# sun_siphon.net
KiCad netlist of a schematic drawn in Altium Designer
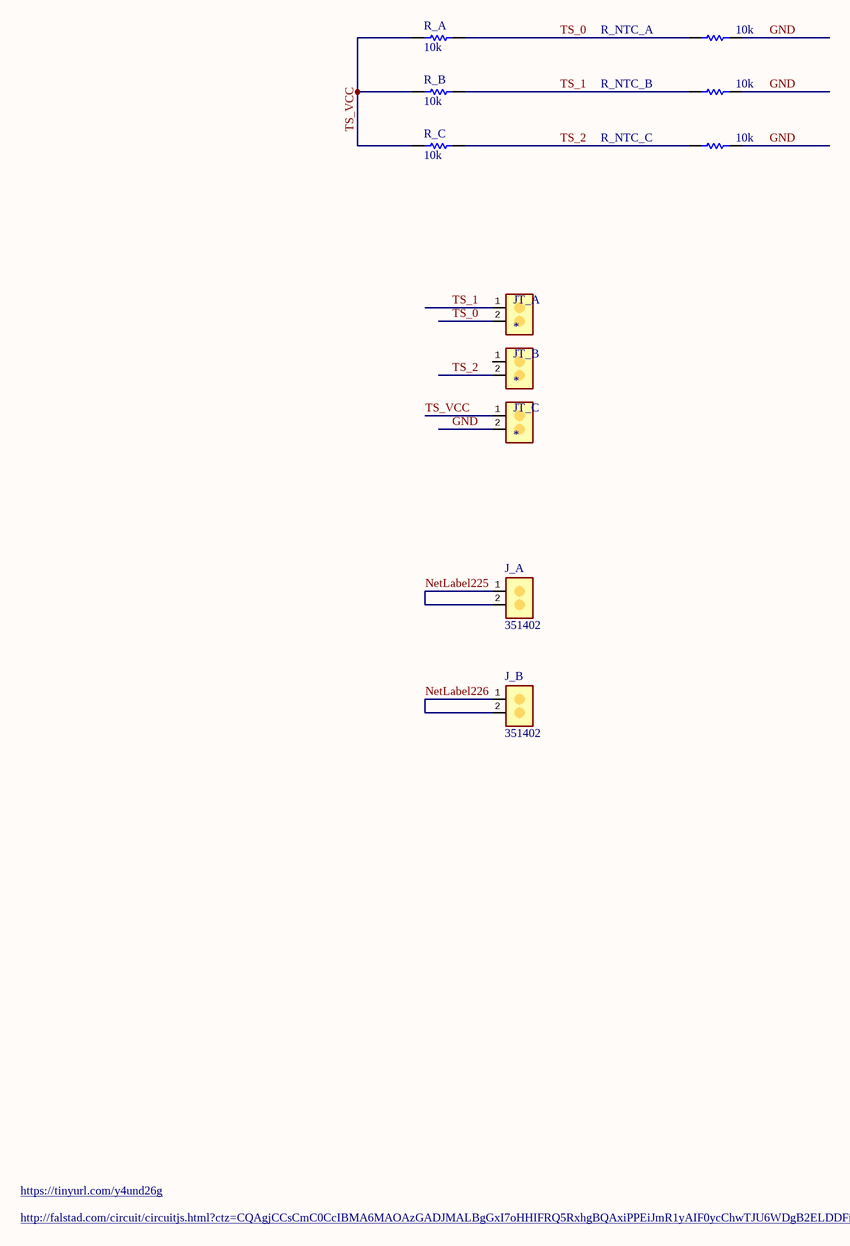
[diagram p0: sun_siphon.SchDoc]

(export (version "E")
  (design (tool "Eeschema 10.0.6"))
  (components
    (comp (ref "JT_A")
      (value "*")
      (footprint "MOLEX_1041880210")
      (description "J - JACK - POWER - MOLEX 1041880210")
      (fields (field (name "LCSC PART #") "C565283"))
      (libsource (lib "*") (part "1041880210"))
    )
    (comp (ref "JT_B")
      (value "*")
      (footprint "MOLEX_1041880210")
      (description "J - JACK - POWER - MOLEX 1041880210")
      (fields (field (name "LCSC PART #") "C565283"))
      (libsource (lib "*") (part "1041880210"))
    )
    (comp (ref "JT_C")
      (value "*")
      (footprint "MOLEX_1041880210")
      (description "J - JACK - POWER - MOLEX 1041880210")
      (fields (field (name "LCSC PART #") "C565283"))
      (libsource (lib "*") (part "1041880210"))
    )
    (comp (ref "J_A")
      (value "351402")
      (footprint "Adels-Contact_351402")
      (description "J - JACK - POWER - SMDflat 545/ 2 - RIGHT - MALE")
      (fields (field (name "LCSC PART #") "X"))
      (libsource (lib "JLC_PCB") (part "351402"))
    )
    (comp (ref "J_B")
      (value "351402")
      (footprint "Adels-Contact_351402")
      (description "J - JACK - POWER - SMDflat 545/ 2 - RIGHT - MALE")
      (fields (field (name "LCSC PART #") "X"))
      (libsource (lib "JLC_PCB") (part "351402"))
    )
    (comp (ref "R_A")
      (value "10k")
      (footprint "R_0402")
      (description "R - RESISTOR - SMD - 10k - 1% - 0402")
      (fields (field (name "LCSC PART #") "C25744") (field (name "Comment") "0402WGF1002TCE"))
      (libsource (lib "JLC_PCB") (part "0402WGF1002TCE"))
    )
    (comp (ref "R_B")
      (value "10k")
      (footprint "R_0402")
      (description "R - RESISTOR - SMD - 10k - 1% - 0402")
      (fields (field (name "LCSC PART #") "C25744") (field (name "Comment") "0402WGF1002TCE"))
      (libsource (lib "JLC_PCB") (part "0402WGF1002TCE"))
    )
    (comp (ref "R_C")
      (value "10k")
      (footprint "R_0402")
      (description "R - RESISTOR - SMD - 10k - 1% - 0402")
      (fields (field (name "LCSC PART #") "C25744") (field (name "Comment") "0402WGF1002TCE"))
      (libsource (lib "JLC_PCB") (part "0402WGF1002TCE"))
    )
    (comp (ref "R_NTC_A")
      (value "10k")
      (footprint "R_0402")
      (description "RT - NTC THERMISTOR - 10k - 1% - 0402")
      (fields (field (name "LCSC PART #") "C77131") (field (name "Comment") "NCP15XH103F03RC"))
      (libsource (lib "JLC_PCB") (part "NCP15XH103F03RC"))
    )
    (comp (ref "R_NTC_B")
      (value "10k")
      (footprint "R_0402")
      (description "RT - NTC THERMISTOR - 10k - 1% - 0402")
      (fields (field (name "LCSC PART #") "C77131") (field (name "Comment") "NCP15XH103F03RC"))
      (libsource (lib "JLC_PCB") (part "NCP15XH103F03RC"))
    )
    (comp (ref "R_NTC_C")
      (value "10k")
      (footprint "R_0402")
      (description "RT - NTC THERMISTOR - 10k - 1% - 0402")
      (fields (field (name "LCSC PART #") "C77131") (field (name "Comment") "NCP15XH103F03RC"))
      (libsource (lib "JLC_PCB") (part "NCP15XH103F03RC"))
    )
  )
  (nets
    (net (code "1") (name "/GND") (class "Default")
      (node (ref "JT_C") (pin "2") (pinfunction "2_2") (pintype "passive"))
      (node (ref "R_NTC_A") (pin "1") (pinfunction "1_1") (pintype "passive"))
      (node (ref "R_NTC_B") (pin "1") (pinfunction "1_1") (pintype "passive"))
      (node (ref "R_NTC_C") (pin "1") (pinfunction "1_1") (pintype "passive"))
    )
    (net (code "2") (name "/NetLabel225") (class "Default")
      (node (ref "J_A") (pin "1") (pinfunction "1_1") (pintype "passive"))
      (node (ref "J_A") (pin "2") (pinfunction "2_2") (pintype "passive"))
    )
    (net (code "3") (name "/NetLabel226") (class "Default")
      (node (ref "J_B") (pin "1") (pinfunction "1_1") (pintype "passive"))
      (node (ref "J_B") (pin "2") (pinfunction "2_2") (pintype "passive"))
    )
    (net (code "4") (name "/TS_0") (class "Default")
      (node (ref "JT_A") (pin "2") (pinfunction "2_2") (pintype "passive"))
      (node (ref "R_A") (pin "2") (pinfunction "2_2") (pintype "passive"))
      (node (ref "R_NTC_A") (pin "2") (pinfunction "2_2") (pintype "passive"))
    )
    (net (code "5") (name "/TS_1") (class "Default")
      (node (ref "JT_A") (pin "1") (pinfunction "1_1") (pintype "passive"))
      (node (ref "R_B") (pin "2") (pinfunction "2_2") (pintype "passive"))
      (node (ref "R_NTC_B") (pin "2") (pinfunction "2_2") (pintype "passive"))
    )
    (net (code "6") (name "/TS_2") (class "Default")
      (node (ref "JT_B") (pin "2") (pinfunction "2_2") (pintype "passive"))
      (node (ref "R_C") (pin "2") (pinfunction "2_2") (pintype "passive"))
      (node (ref "R_NTC_C") (pin "2") (pinfunction "2_2") (pintype "passive"))
    )
    (net (code "7") (name "/TS_VCC") (class "Default")
      (node (ref "JT_C") (pin "1") (pinfunction "1_1") (pintype "passive"))
      (node (ref "R_A") (pin "1") (pinfunction "1_1") (pintype "passive"))
      (node (ref "R_B") (pin "1") (pinfunction "1_1") (pintype "passive"))
      (node (ref "R_C") (pin "1") (pinfunction "1_1") (pintype "passive"))
    )
    (net (code "8") (name "unconnected-(JT_B-Pad1)") (class "Default")
      (node (ref "JT_B") (pin "1") (pinfunction "1_1") (pintype "passive"))
    )
  )
)
